# SAMC21_one.net
KiCad netlist of a schematic drawn in Altium Designer
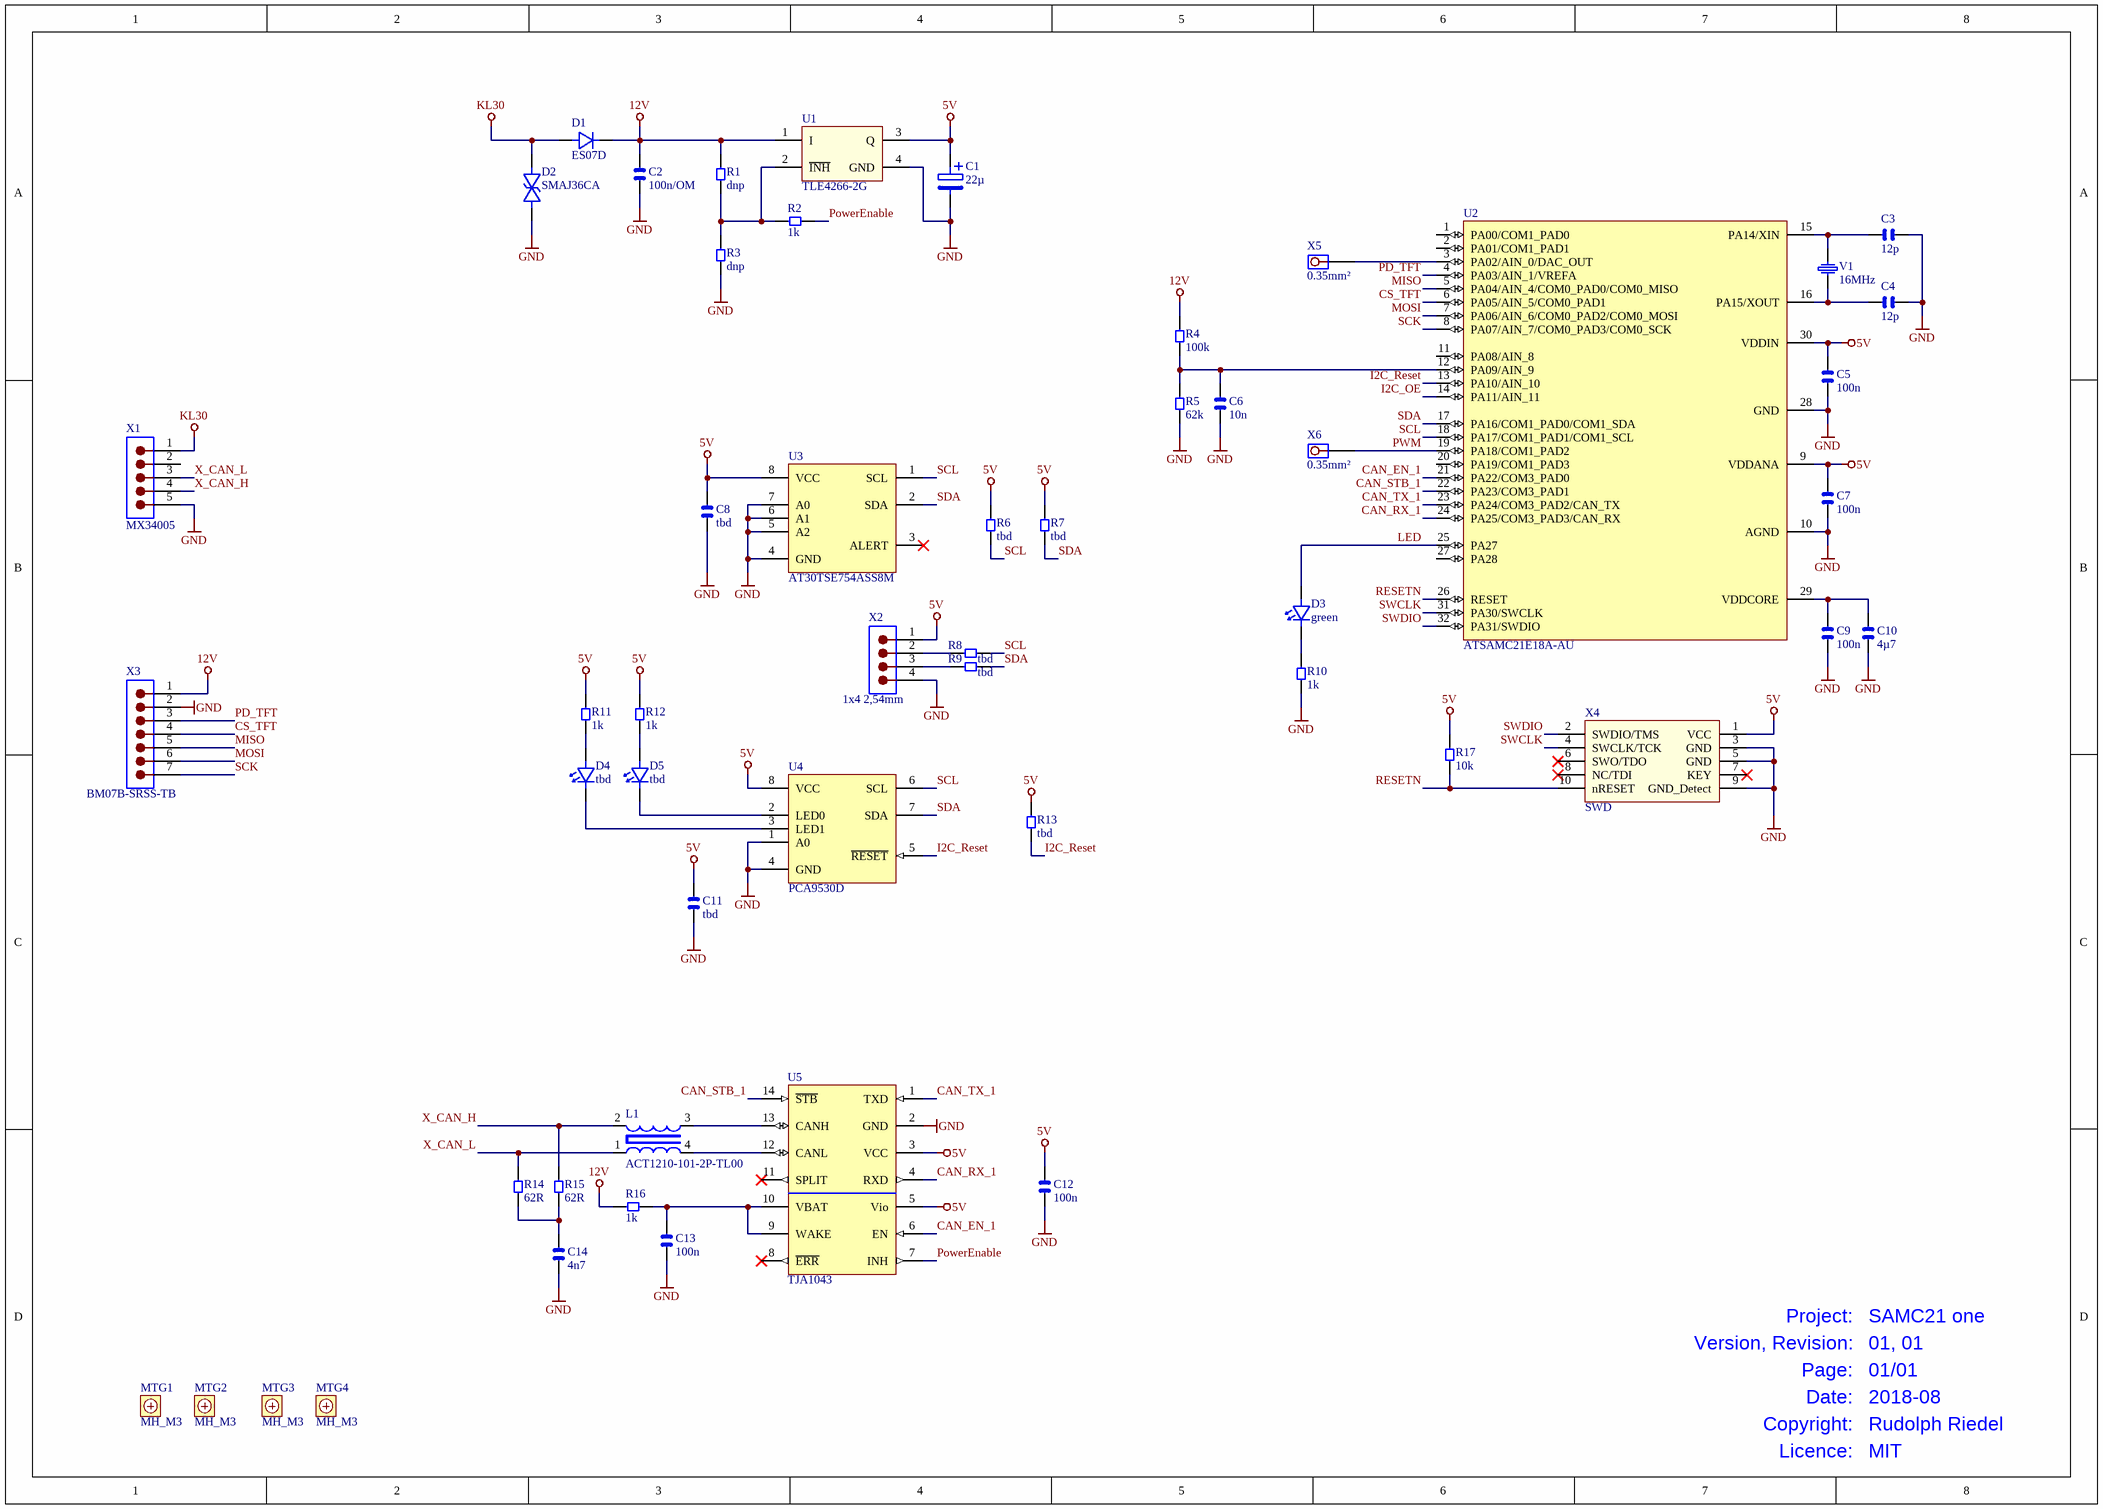
[diagram p0: SAMC21_one.SchDoc]

(export (version "E")
  (design (tool "Eeschema 10.0.6"))
  (components
    (comp (ref "C1")
      (value "22µ")
      (footprint "CAPMP3528X21N")
      (description "Tantalkondensator SMD Bauform B")
      (fields (field (name "PART NUMBER") "CAPMP_B") (field (name "ERSTELLER") "rriedel"))
      (libsource (lib "HW-Labor_GF") (part "CAPP_2_V2"))
    )
    (comp (ref "C2")
      (value "100n/OM")
      (footprint "CAPC2012X14L")
      (description "0805 Chip Capacitor")
      (fields (field (name "PART NUMBER") "CAPC_0805") (field (name "ERSTELLER") "rriedel"))
      (libsource (lib "HW-Labor_GF") (part "CAP_2_V2"))
    )
    (comp (ref "C3")
      (value "12p")
      (footprint "CAPC2012X14L")
      (description "0805 Chip Capacitor")
      (fields (field (name "PART NUMBER") "CAPC_0805") (field (name "ERSTELLER") "rriedel"))
      (libsource (lib "HW-Labor_GF") (part "CAP_2_V2"))
    )
    (comp (ref "C4")
      (value "12p")
      (footprint "CAPC2012X14L")
      (description "0805 Chip Capacitor")
      (fields (field (name "PART NUMBER") "CAPC_0805") (field (name "ERSTELLER") "rriedel"))
      (libsource (lib "HW-Labor_GF") (part "CAP_2_V2"))
    )
    (comp (ref "C5")
      (value "100n")
      (footprint "CAPC1608X09L")
      (description "0603 Chip Capacitor")
      (fields (field (name "PART NUMBER") "CAPC_0603") (field (name "ERSTELLER") "rriedel"))
      (libsource (lib "HW-Labor_GF") (part "CAP_2_V2"))
    )
    (comp (ref "C6")
      (value "10n")
      (footprint "CAPC2012X14L")
      (description "0805 Chip Capacitor")
      (fields (field (name "PART NUMBER") "CAPC_0805") (field (name "ERSTELLER") "rriedel"))
      (libsource (lib "HW-Labor_GF") (part "CAP_2_V2"))
    )
    (comp (ref "C7")
      (value "100n")
      (footprint "CAPC1608X09L")
      (description "0603 Chip Capacitor")
      (fields (field (name "PART NUMBER") "CAPC_0603") (field (name "ERSTELLER") "rriedel"))
      (libsource (lib "HW-Labor_GF") (part "CAP_2_V2"))
    )
    (comp (ref "C8")
      (value "tbd")
      (footprint "CAPC2012X14L")
      (description "0805 Chip Capacitor")
      (fields (field (name "PART NUMBER") "CAPC_0805") (field (name "ERSTELLER") "rriedel"))
      (libsource (lib "HW-Labor_GF") (part "CAP_2_V2"))
    )
    (comp (ref "C9")
      (value "100n")
      (footprint "CAPC1608X09L")
      (description "0603 Chip Capacitor")
      (fields (field (name "PART NUMBER") "CAPC_0603") (field (name "ERSTELLER") "rriedel"))
      (libsource (lib "HW-Labor_GF") (part "CAP_2_V2"))
    )
    (comp (ref "C10")
      (value "4µ7")
      (footprint "CAPC2012X14L")
      (description "0805 Chip Capacitor")
      (fields (field (name "PART NUMBER") "CAPC_0805") (field (name "ERSTELLER") "rriedel"))
      (libsource (lib "HW-Labor_GF") (part "CAP_2_V2"))
    )
    (comp (ref "C11")
      (value "tbd")
      (footprint "CAPC2012X14L")
      (description "0805 Chip Capacitor")
      (fields (field (name "PART NUMBER") "CAPC_0805") (field (name "ERSTELLER") "rriedel"))
      (libsource (lib "HW-Labor_GF") (part "CAP_2_V2"))
    )
    (comp (ref "C12")
      (value "100n")
      (footprint "CAPC2012X14L")
      (description "0805 Chip Capacitor")
      (fields (field (name "PART NUMBER") "CAPC_0805") (field (name "ERSTELLER") "rriedel"))
      (libsource (lib "HW-Labor_GF") (part "CAP_2_V2"))
    )
    (comp (ref "C13")
      (value "100n")
      (footprint "CAPC2012X14L")
      (description "0805 Chip Capacitor")
      (fields (field (name "PART NUMBER") "CAPC_0805") (field (name "ERSTELLER") "rriedel"))
      (libsource (lib "HW-Labor_GF") (part "CAP_2_V2"))
    )
    (comp (ref "C14")
      (value "4n7")
      (footprint "CAPC2012X14L")
      (description "0805 Chip Capacitor")
      (fields (field (name "PART NUMBER") "CAPC_0805") (field (name "ERSTELLER") "rriedel"))
      (libsource (lib "HW-Labor_GF") (part "CAP_2_V2"))
    )
    (comp (ref "D1")
      (value "ES07D")
      (footprint "DIOM2818X11N")
      (description "Ultrafast Rectifier Surface Mount,  IF 0.5A, VR 100V, DO-219AB, AEC-Q101")
      (fields (field (name "ERSTELLER") "rriedel"))
      (libsource (lib "HW-Labor_GF") (part "Diode_A2_K1"))
    )
    (comp (ref "D2")
      (value "SMAJ36CA")
      (footprint "DIOM5226X23N")
      (description "Transildiode Bidirectional 400W 36V")
      (fields (field (name "ERSTELLER") "rriedel"))
      (libsource (lib "HW-Labor_GF") (part "SMAJxxCA"))
    )
    (comp (ref "D3")
      (value "green")
      (footprint "DIOC2012X10N")
      (description "LED, 0805")
      (fields (field (name "PART NUMBER") "LED_0805") (field (name "ERSTELLER") "rriedel"))
      (libsource (lib "HW-Labor_GF") (part "LED_generic"))
    )
    (comp (ref "D4")
      (value "tbd")
      (footprint "DIOC2012X10N")
      (description "LED, 0805")
      (fields (field (name "PART NUMBER") "LED_0805") (field (name "ERSTELLER") "rriedel"))
      (libsource (lib "HW-Labor_GF") (part "LED_generic"))
    )
    (comp (ref "D5")
      (value "tbd")
      (footprint "DIOC2012X10N")
      (description "LED, 0805")
      (fields (field (name "PART NUMBER") "LED_0805") (field (name "ERSTELLER") "rriedel"))
      (libsource (lib "HW-Labor_GF") (part "LED_generic"))
    )
    (comp (ref "L1")
      (value "ACT1210-101-2P-TL00")
      (footprint "ACT1210")
      (description "Common Mode Filter,  -50°C ... +150°C, AEC-Q200")
      (fields
        (field (name "DISTRIBUTOR_1_PART_NUMBER") "2442838")
        (field (name "DISTRIBUTOR_2_PART_NUMBER") "445-172386-1-ND")
        (field (name "ERSTELLER") "rriedel")
      )
      (libsource (lib "HW-Labor_GF") (part "CAN_DROSSEL"))
    )
    (comp (ref "MTG1")
      (value "MH_M3")
      (footprint "HOLE_3_2MM")
      (description "Mounting-Hole for M3 screws")
      (fields (field (name "ERSTELLER") "rriedel"))
      (libsource (lib "HW-Labor_GF") (part "MTG_V1"))
    )
    (comp (ref "MTG2")
      (value "MH_M3")
      (footprint "HOLE_3_2MM")
      (description "Mounting-Hole for M3 screws")
      (fields (field (name "ERSTELLER") "rriedel"))
      (libsource (lib "HW-Labor_GF") (part "MTG_V1"))
    )
    (comp (ref "MTG3")
      (value "MH_M3")
      (footprint "HOLE_3_2MM")
      (description "Mounting-Hole for M3 screws")
      (fields (field (name "ERSTELLER") "rriedel"))
      (libsource (lib "HW-Labor_GF") (part "MTG_V1"))
    )
    (comp (ref "MTG4")
      (value "MH_M3")
      (footprint "HOLE_3_2MM")
      (description "Mounting-Hole for M3 screws")
      (fields (field (name "ERSTELLER") "rriedel"))
      (libsource (lib "HW-Labor_GF") (part "MTG_V1"))
    )
    (comp (ref "R1")
      (value "dnp")
      (footprint "RESC2012X06L")
      (description "0805 Chip Resistor")
      (fields (field (name "PART NUMBER") "RESC_0805") (field (name "ERSTELLER") "rriedel"))
      (libsource (lib "HW-Labor_GF") (part "RES_2_V2"))
    )
    (comp (ref "R2")
      (value "1k")
      (footprint "RESC2012X06L")
      (description "0805 Chip Resistor")
      (fields (field (name "PART NUMBER") "RESC_0805") (field (name "ERSTELLER") "rriedel"))
      (libsource (lib "HW-Labor_GF") (part "RES_2_V2"))
    )
    (comp (ref "R3")
      (value "dnp")
      (footprint "RESC2012X06L")
      (description "0805 Chip Resistor")
      (fields (field (name "PART NUMBER") "RESC_0805") (field (name "ERSTELLER") "rriedel"))
      (libsource (lib "HW-Labor_GF") (part "RES_2_V2"))
    )
    (comp (ref "R4")
      (value "100k")
      (footprint "RESC2012X06L")
      (description "0805 Chip Resistor")
      (fields (field (name "PART NUMBER") "RESC_0805") (field (name "ERSTELLER") "rriedel"))
      (libsource (lib "HW-Labor_GF") (part "RES_2_V2"))
    )
    (comp (ref "R5")
      (value "62k")
      (footprint "RESC2012X06L")
      (description "0805 Chip Resistor")
      (fields (field (name "PART NUMBER") "RESC_0805") (field (name "ERSTELLER") "rriedel"))
      (libsource (lib "HW-Labor_GF") (part "RES_2_V2"))
    )
    (comp (ref "R6")
      (value "tbd")
      (footprint "RESC2012X06L")
      (description "0805 Chip Resistor")
      (fields (field (name "PART NUMBER") "RESC_0805") (field (name "ERSTELLER") "rriedel"))
      (libsource (lib "HW-Labor_GF") (part "RES_2_V2"))
    )
    (comp (ref "R7")
      (value "tbd")
      (footprint "RESC2012X06L")
      (description "0805 Chip Resistor")
      (fields (field (name "PART NUMBER") "RESC_0805") (field (name "ERSTELLER") "rriedel"))
      (libsource (lib "HW-Labor_GF") (part "RES_2_V2"))
    )
    (comp (ref "R8")
      (value "tbd")
      (footprint "RESC2012X06L")
      (description "0805 Chip Resistor")
      (fields (field (name "PART NUMBER") "RESC_0805") (field (name "ERSTELLER") "rriedel"))
      (libsource (lib "HW-Labor_GF") (part "RES_2_V2"))
    )
    (comp (ref "R9")
      (value "tbd")
      (footprint "RESC2012X06L")
      (description "0805 Chip Resistor")
      (fields (field (name "PART NUMBER") "RESC_0805") (field (name "ERSTELLER") "rriedel"))
      (libsource (lib "HW-Labor_GF") (part "RES_2_V2"))
    )
    (comp (ref "R10")
      (value "1k")
      (footprint "RESC2012X06L")
      (description "0805 Chip Resistor")
      (fields (field (name "PART NUMBER") "RESC_0805") (field (name "ERSTELLER") "rriedel"))
      (libsource (lib "HW-Labor_GF") (part "RES_2_V2"))
    )
    (comp (ref "R11")
      (value "1k")
      (footprint "RESC2012X06L")
      (description "0805 Chip Resistor")
      (fields (field (name "PART NUMBER") "RESC_0805") (field (name "ERSTELLER") "rriedel"))
      (libsource (lib "HW-Labor_GF") (part "RES_2_V2"))
    )
    (comp (ref "R12")
      (value "1k")
      (footprint "RESC2012X06L")
      (description "0805 Chip Resistor")
      (fields (field (name "PART NUMBER") "RESC_0805") (field (name "ERSTELLER") "rriedel"))
      (libsource (lib "HW-Labor_GF") (part "RES_2_V2"))
    )
    (comp (ref "R13")
      (value "tbd")
      (footprint "RESC2012X06L")
      (description "0805 Chip Resistor")
      (fields (field (name "PART NUMBER") "RESC_0805") (field (name "ERSTELLER") "rriedel"))
      (libsource (lib "HW-Labor_GF") (part "RES_2_V2"))
    )
    (comp (ref "R14")
      (value "62R")
      (footprint "RESC3216X07N")
      (description "1206 Chip Resistor")
      (fields (field (name "PART NUMBER") "RESC_1206") (field (name "ERSTELLER") "rriedel"))
      (libsource (lib "HW-Labor_GF") (part "RES_2_V2"))
    )
    (comp (ref "R15")
      (value "62R")
      (footprint "RESC3216X07N")
      (description "1206 Chip Resistor")
      (fields (field (name "PART NUMBER") "RESC_1206") (field (name "ERSTELLER") "rriedel"))
      (libsource (lib "HW-Labor_GF") (part "RES_2_V2"))
    )
    (comp (ref "R16")
      (value "1k")
      (footprint "RESC2012X06L")
      (description "0805 Chip Resistor")
      (fields (field (name "PART NUMBER") "RESC_0805") (field (name "ERSTELLER") "rriedel"))
      (libsource (lib "HW-Labor_GF") (part "RES_2_V2"))
    )
    (comp (ref "R17")
      (value "10k")
      (footprint "RESC2012X06L")
      (description "0805 Chip Resistor")
      (fields (field (name "PART NUMBER") "RESC_0805") (field (name "ERSTELLER") "rriedel"))
      (libsource (lib "HW-Labor_GF") (part "RES_2_V2"))
    )
    (comp (ref "U1")
      (value "TLE4266-2G")
      (footprint "SOT230P700X180-4N")
      (description "150 mA LDO, Vout = 5,0V, 2%, Enable")
      (fields (field (name "ERSTELLER") "rriedel"))
      (libsource (lib "HW-Labor_GF") (part "LDO_SOT223_EN"))
    )
    (comp (ref "U2")
      (value "ATSAMC21E18A-AU")
      (footprint "TQFP80P900X900X120-32N")
      (description "32-bit Microcontroller, 48MHz Cortex M0, 256k FLASH,  1x CAN-FD, -40…85°C")
      (fields (field (name "ERSTELLER") "rriedel"))
      (libsource (lib "HW-Labor_GF") (part "ATSAMC21E1xA"))
    )
    (comp (ref "U3")
      (value "AT30TSE754ASS8M")
      (footprint "SOIC127P600X175-8N")
      (description "I2C Digital Temperature Sensor and EEPROM")
      (fields (field (name "ERSTELLER") "rriedel"))
      (libsource (lib "HW-Labor_GF") (part "AT30TSE75xAxx8M"))
    )
    (comp (ref "U4")
      (value "PCA9530D")
      (footprint "TSOP65P640X120-8N")
      (description "2-bit I2C LED dimmer")
      (fields (field (name "ERSTELLER") "rriedel"))
      (libsource (lib "HW-Labor_GF") (part "PCA9530"))
    )
    (comp (ref "U5")
      (value "TJA1043")
      (footprint "SOIC127P600X175-14N")
      (description "HS Can Transceiver with wake-up Tvj= -40 to 150 °C")
      (fields (field (name "PART NUMBER") "TJA1043T") (field (name "ERSTELLER") "rriedel"))
      (libsource (lib "HW-Labor_GF") (part "TJA1043"))
    )
    (comp (ref "V1")
      (value "16MHz")
      (footprint "NX3225Gx")
      (description "16.000MHz Crystal SMD, 3.2x2.5mm, 8pF, 50ppm,  -40..+150°C")
      (fields
        (field (name "PART NUMBER") "NX3225GB-16.000000MHZ")
        (field (name "DISTRIBUTOR_1_PART_NUMBER") "644-1233-1-ND")
        (field (name "ERSTELLER") "rriedel")
      )
      (libsource (lib "HW-Labor_GF") (part "XTAL_2_V1"))
    )
    (comp (ref "X1")
      (value "MX34005")
      (footprint "MX34005")
      (description "PCB Header, Automotive, single row, 5 pins")
      (fields (field (name "ERSTELLER") "rriedel"))
      (libsource (lib "HW-Labor_GF") (part "CONM_1x5_V2"))
    )
    (comp (ref "X2")
      (value "1x4 2,54mm")
      (footprint "PINH_1x04_2_54mm")
      (description "Pin-Header 2,54 mm 4pins")
      (fields (field (name "PART NUMBER") "PINH_1x4_2_54") (field (name "ERSTELLER") "rriedel"))
      (libsource (lib "HW-Labor_GF") (part "CONM_1x4_V2"))
    )
    (comp (ref "X3")
      (value "BM07B-SRSS-TB")
      (footprint "BM07B-SRSS-TB")
      (description "JST PCB Header SH, 7pins, 1,0mm, -25°C to +85°C")
      (fields
        (field (name "PART NUMBER") "SM07B-SRSS-TB")
        (field (name "DISTRIBUTOR_1_PART_NUMBER") "546-8798")
        (field (name "ERSTELLER") "rriedel")
      )
      (libsource (lib "HW-Labor_GF") (part "CONM_1x7_V2"))
    )
    (comp (ref "X4")
      (value "SWD")
      (footprint "FTSH-105-01-L-DV-K")
      (description "ARM Debug-Header 2x5 1,27 mm")
      (fields (field (name "ERSTELLER") "rriedel"))
      (libsource (lib "HW-Labor_GF") (part "SWD"))
    )
    (comp (ref "X5")
      (value "0.35mm²")
      (footprint "PAD035X160")
      (description "Wire pad 0,35mm²")
      (fields (field (name "PART NUMBER") "PAD035") (field (name "ERSTELLER") "rriedel"))
      (libsource (lib "HW-Labor_GF") (part "PADxxx_1"))
    )
    (comp (ref "X6")
      (value "0.35mm²")
      (footprint "PAD035X160")
      (description "Wire pad 0,35mm²")
      (fields (field (name "PART NUMBER") "PAD035") (field (name "ERSTELLER") "rriedel"))
      (libsource (lib "HW-Labor_GF") (part "PADxxx_1"))
    )
  )
  (nets
    (net (code "1") (name "/CAN_EN_1") (class "Default")
      (node (ref "U2") (pin "21") (pinfunction "PA22/COM3_PAD0_21") (pintype "bidirectional"))
      (node (ref "U5") (pin "6") (pinfunction "EN_6") (pintype "input"))
    )
    (net (code "2") (name "/CAN_RX_1") (class "Default")
      (node (ref "U2") (pin "24") (pinfunction "PA25/COM3_PAD3/CAN_RX_24") (pintype "bidirectional"))
      (node (ref "U5") (pin "4") (pinfunction "RXD_4") (pintype "output"))
    )
    (net (code "3") (name "/CAN_STB_1") (class "Default")
      (node (ref "U2") (pin "22") (pinfunction "PA23/COM3_PAD1_22") (pintype "bidirectional"))
      (node (ref "U5") (pin "14") (pinfunction "~{STB}_14") (pintype "input"))
    )
    (net (code "4") (name "/CAN_TX_1") (class "Default")
      (node (ref "U2") (pin "23") (pinfunction "PA24/COM3_PAD2/CAN_TX_23") (pintype "bidirectional"))
      (node (ref "U5") (pin "1") (pinfunction "TXD_1") (pintype "input"))
    )
    (net (code "5") (name "/CS_TFT") (class "Default")
      (node (ref "U2") (pin "6") (pinfunction "PA05/AIN_5/COM0_PAD1_6") (pintype "bidirectional"))
      (node (ref "X3") (pin "4") (pinfunction "4_4") (pintype "passive"))
    )
    (net (code "6") (name "/I2C_OE") (class "Default")
      (node (ref "U2") (pin "14") (pinfunction "PA11/AIN_11_14") (pintype "bidirectional"))
    )
    (net (code "7") (name "/I2C_Reset") (class "Default")
      (node (ref "R13") (pin "1") (pinfunction "1_1") (pintype "passive"))
      (node (ref "U2") (pin "13") (pinfunction "PA10/AIN_10_13") (pintype "bidirectional"))
      (node (ref "U4") (pin "5") (pinfunction "RESET_5") (pintype "input"))
    )
    (net (code "8") (name "/LED") (class "Default")
      (node (ref "D3") (pin "2") (pinfunction "2_2") (pintype "passive"))
      (node (ref "U2") (pin "25") (pinfunction "PA27_25") (pintype "bidirectional"))
    )
    (net (code "9") (name "/MISO") (class "Default")
      (node (ref "U2") (pin "5") (pinfunction "PA04/AIN_4/COM0_PAD0/COM0_MISO_5") (pintype "bidirectional"))
      (node (ref "X3") (pin "5") (pinfunction "5_5") (pintype "passive"))
    )
    (net (code "10") (name "/MOSI") (class "Default")
      (node (ref "U2") (pin "7") (pinfunction "PA06/AIN_6/COM0_PAD2/COM0_MOSI_7") (pintype "bidirectional"))
      (node (ref "X3") (pin "6") (pinfunction "6_6") (pintype "passive"))
    )
    (net (code "11") (name "/PD_TFT") (class "Default")
      (node (ref "U2") (pin "4") (pinfunction "PA03/AIN_1/VREFA_4") (pintype "bidirectional"))
      (node (ref "X3") (pin "3") (pinfunction "3_3") (pintype "passive"))
    )
    (net (code "12") (name "/PWM") (class "Default")
      (node (ref "U2") (pin "19") (pinfunction "PA18/COM1_PAD2_19") (pintype "bidirectional"))
      (node (ref "X6") (pin "1") (pinfunction "1_1") (pintype "passive"))
    )
    (net (code "13") (name "/PowerEnable") (class "Default")
      (node (ref "R2") (pin "1") (pinfunction "1_1") (pintype "passive"))
      (node (ref "U5") (pin "7") (pinfunction "INH_7") (pintype "output"))
    )
    (net (code "14") (name "/RESETN") (class "Default")
      (node (ref "R17") (pin "1") (pinfunction "1_1") (pintype "passive"))
      (node (ref "U2") (pin "26") (pinfunction "RESET_26") (pintype "bidirectional"))
      (node (ref "X4") (pin "10") (pinfunction "nRESET_10") (pintype "passive"))
    )
    (net (code "15") (name "/SCK") (class "Default")
      (node (ref "U2") (pin "8") (pinfunction "PA07/AIN_7/COM0_PAD3/COM0_SCK_8") (pintype "bidirectional"))
      (node (ref "X3") (pin "7") (pinfunction "7_7") (pintype "passive"))
    )
    (net (code "16") (name "/SCL") (class "Default")
      (node (ref "R6") (pin "1") (pinfunction "1_1") (pintype "passive"))
      (node (ref "R8") (pin "2") (pinfunction "2_2") (pintype "passive"))
      (node (ref "U2") (pin "18") (pinfunction "PA17/COM1_PAD1/COM1_SCL_18") (pintype "bidirectional"))
      (node (ref "U3") (pin "1") (pinfunction "SCL_1") (pintype "passive"))
      (node (ref "U4") (pin "6") (pinfunction "SCL_6") (pintype "passive"))
    )
    (net (code "17") (name "/SDA") (class "Default")
      (node (ref "R7") (pin "1") (pinfunction "1_1") (pintype "passive"))
      (node (ref "R9") (pin "2") (pinfunction "2_2") (pintype "passive"))
      (node (ref "U2") (pin "17") (pinfunction "PA16/COM1_PAD0/COM1_SDA_17") (pintype "bidirectional"))
      (node (ref "U3") (pin "2") (pinfunction "SDA_2") (pintype "passive"))
      (node (ref "U4") (pin "7") (pinfunction "SDA_7") (pintype "passive"))
    )
    (net (code "18") (name "/SWCLK") (class "Default")
      (node (ref "U2") (pin "31") (pinfunction "PA30/SWCLK_31") (pintype "bidirectional"))
      (node (ref "X4") (pin "4") (pinfunction "SWCLK/TCK_4") (pintype "passive"))
    )
    (net (code "19") (name "/SWDIO") (class "Default")
      (node (ref "U2") (pin "32") (pinfunction "PA31/SWDIO_32") (pintype "bidirectional"))
      (node (ref "X4") (pin "2") (pinfunction "SWDIO/TMS_2") (pintype "passive"))
    )
    (net (code "20") (name "/X_CAN_H") (class "Default")
      (node (ref "L1") (pin "2") (pintype "passive"))
      (node (ref "R15") (pin "2") (pinfunction "2_2") (pintype "passive"))
      (node (ref "X1") (pin "4") (pinfunction "4_4") (pintype "passive"))
    )
    (net (code "21") (name "/X_CAN_L") (class "Default")
      (node (ref "L1") (pin "1") (pintype "passive"))
      (node (ref "R14") (pin "2") (pinfunction "2_2") (pintype "passive"))
      (node (ref "X1") (pin "3") (pinfunction "3_3") (pintype "passive"))
    )
    (net (code "22") (name "5V") (class "Default")
      (node (ref "C1") (pin "1") (pinfunction "1_1") (pintype "passive"))
      (node (ref "C11") (pin "2") (pinfunction "2_2") (pintype "passive"))
      (node (ref "C12") (pin "2") (pinfunction "2_2") (pintype "passive"))
      (node (ref "C5") (pin "2") (pinfunction "2_2") (pintype "passive"))
      (node (ref "C7") (pin "2") (pinfunction "2_2") (pintype "passive"))
      (node (ref "C8") (pin "2") (pinfunction "2_2") (pintype "passive"))
      (node (ref "R11") (pin "2") (pinfunction "2_2") (pintype "passive"))
      (node (ref "R12") (pin "2") (pinfunction "2_2") (pintype "passive"))
      (node (ref "R13") (pin "2") (pinfunction "2_2") (pintype "passive"))
      (node (ref "R17") (pin "2") (pinfunction "2_2") (pintype "passive"))
      (node (ref "R6") (pin "2") (pinfunction "2_2") (pintype "passive"))
      (node (ref "R7") (pin "2") (pinfunction "2_2") (pintype "passive"))
      (node (ref "U1") (pin "3") (pinfunction "Q_3") (pintype "passive"))
      (node (ref "U2") (pin "30") (pinfunction "VDDIN_30") (pintype "power_in"))
      (node (ref "U2") (pin "9") (pinfunction "VDDANA_9") (pintype "power_in"))
      (node (ref "U3") (pin "8") (pinfunction "VCC_8") (pintype "power_in"))
      (node (ref "U4") (pin "8") (pinfunction "VCC_8") (pintype "power_in"))
      (node (ref "U5") (pin "3") (pinfunction "VCC_3") (pintype "power_in"))
      (node (ref "U5") (pin "5") (pinfunction "Vio_5") (pintype "power_in"))
      (node (ref "X2") (pin "1") (pinfunction "1_1") (pintype "passive"))
      (node (ref "X4") (pin "1") (pinfunction "VCC_1") (pintype "power_in"))
    )
    (net (code "23") (name "12V") (class "Default")
      (node (ref "C2") (pin "2") (pinfunction "2_2") (pintype "passive"))
      (node (ref "D1") (pin "1") (pinfunction "1_1") (pintype "passive"))
      (node (ref "R1") (pin "2") (pinfunction "2_2") (pintype "passive"))
      (node (ref "R16") (pin "1") (pinfunction "1_1") (pintype "passive"))
      (node (ref "R4") (pin "2") (pinfunction "2_2") (pintype "passive"))
      (node (ref "U1") (pin "1") (pinfunction "I_1") (pintype "passive"))
      (node (ref "X3") (pin "1") (pinfunction "1_1") (pintype "passive"))
    )
    (net (code "24") (name "GND") (class "Default")
      (node (ref "C1") (pin "2") (pinfunction "2_2") (pintype "passive"))
      (node (ref "C10") (pin "1") (pinfunction "1_1") (pintype "passive"))
      (node (ref "C11") (pin "1") (pinfunction "1_1") (pintype "passive"))
      (node (ref "C12") (pin "1") (pinfunction "1_1") (pintype "passive"))
      (node (ref "C13") (pin "1") (pinfunction "1_1") (pintype "passive"))
      (node (ref "C14") (pin "1") (pinfunction "1_1") (pintype "passive"))
      (node (ref "C2") (pin "1") (pinfunction "1_1") (pintype "passive"))
      (node (ref "C3") (pin "2") (pinfunction "2_2") (pintype "passive"))
      (node (ref "C4") (pin "2") (pinfunction "2_2") (pintype "passive"))
      (node (ref "C5") (pin "1") (pinfunction "1_1") (pintype "passive"))
      (node (ref "C6") (pin "1") (pinfunction "1_1") (pintype "passive"))
      (node (ref "C7") (pin "1") (pinfunction "1_1") (pintype "passive"))
      (node (ref "C8") (pin "1") (pinfunction "1_1") (pintype "passive"))
      (node (ref "C9") (pin "1") (pinfunction "1_1") (pintype "passive"))
      (node (ref "D2") (pin "1") (pinfunction "1_1") (pintype "passive"))
      (node (ref "R10") (pin "1") (pinfunction "1_1") (pintype "passive"))
      (node (ref "R3") (pin "1") (pinfunction "1_1") (pintype "passive"))
      (node (ref "R5") (pin "1") (pinfunction "1_1") (pintype "passive"))
      (node (ref "U1") (pin "4") (pinfunction "GND_4") (pintype "passive"))
      (node (ref "U2") (pin "10") (pinfunction "AGND_10") (pintype "power_in"))
      (node (ref "U2") (pin "28") (pinfunction "GND_28") (pintype "power_in"))
      (node (ref "U3") (pin "4") (pinfunction "GND_4") (pintype "power_in"))
      (node (ref "U3") (pin "5") (pinfunction "A2_5") (pintype "passive"))
      (node (ref "U3") (pin "6") (pinfunction "A1_6") (pintype "passive"))
      (node (ref "U3") (pin "7") (pinfunction "A0_7") (pintype "passive"))
      (node (ref "U4") (pin "1") (pinfunction "A0_1") (pintype "passive"))
      (node (ref "U4") (pin "4") (pinfunction "GND_4") (pintype "power_in"))
      (node (ref "U5") (pin "2") (pinfunction "GND_2") (pintype "power_in"))
      (node (ref "X1") (pin "5") (pinfunction "5_5") (pintype "passive"))
      (node (ref "X2") (pin "4") (pinfunction "4_4") (pintype "passive"))
      (node (ref "X3") (pin "2") (pinfunction "2_2") (pintype "passive"))
      (node (ref "X4") (pin "3") (pinfunction "GND_3") (pintype "power_in"))
      (node (ref "X4") (pin "5") (pinfunction "GND_5") (pintype "power_in"))
      (node (ref "X4") (pin "9") (pinfunction "GND_Detect_9") (pintype "power_in"))
    )
    (net (code "25") (name "KL30") (class "Default")
      (node (ref "D1") (pin "2") (pinfunction "2_2") (pintype "passive"))
      (node (ref "D2") (pin "2") (pinfunction "2_2") (pintype "passive"))
      (node (ref "X1") (pin "1") (pinfunction "1_1") (pintype "passive"))
    )
    (net (code "26") (name "Net-(C14-Pad2)") (class "Default")
      (node (ref "C14") (pin "2") (pinfunction "2_2") (pintype "passive"))
      (node (ref "R14") (pin "1") (pinfunction "1_1") (pintype "passive"))
      (node (ref "R15") (pin "1") (pinfunction "1_1") (pintype "passive"))
    )
    (net (code "27") (name "Net-(D3-Pad1)") (class "Default")
      (node (ref "D3") (pin "1") (pinfunction "1_1") (pintype "passive"))
      (node (ref "R10") (pin "2") (pinfunction "2_2") (pintype "passive"))
    )
    (net (code "28") (name "Net-(D4-Pad2)") (class "Default")
      (node (ref "D4") (pin "2") (pinfunction "2_2") (pintype "passive"))
      (node (ref "R11") (pin "1") (pinfunction "1_1") (pintype "passive"))
    )
    (net (code "29") (name "Net-(D5-Pad2)") (class "Default")
      (node (ref "D5") (pin "2") (pinfunction "2_2") (pintype "passive"))
      (node (ref "R12") (pin "1") (pinfunction "1_1") (pintype "passive"))
    )
    (net (code "30") (name "Net-(R8-Pad1)") (class "Default")
      (node (ref "R8") (pin "1") (pinfunction "1_1") (pintype "passive"))
      (node (ref "X2") (pin "2") (pinfunction "2_2") (pintype "passive"))
    )
    (net (code "31") (name "Net-(R9-Pad1)") (class "Default")
      (node (ref "R9") (pin "1") (pinfunction "1_1") (pintype "passive"))
      (node (ref "X2") (pin "3") (pinfunction "3_3") (pintype "passive"))
    )
    (net (code "32") (name "Net-(U1-~{INH})") (class "Default")
      (node (ref "R1") (pin "1") (pinfunction "1_1") (pintype "passive"))
      (node (ref "R2") (pin "2") (pinfunction "2_2") (pintype "passive"))
      (node (ref "R3") (pin "2") (pinfunction "2_2") (pintype "passive"))
      (node (ref "U1") (pin "2") (pinfunction "~{INH}_2") (pintype "passive"))
    )
    (net (code "33") (name "Net-(U2-PA02{slash}AIN_0{slash}DAC_OUT)") (class "Default")
      (node (ref "U2") (pin "3") (pinfunction "PA02/AIN_0/DAC_OUT_3") (pintype "bidirectional"))
      (node (ref "X5") (pin "1") (pinfunction "1_1") (pintype "passive"))
    )
    (net (code "34") (name "Net-(U2-PA09{slash}AIN_9)") (class "Default")
      (node (ref "C6") (pin "2") (pinfunction "2_2") (pintype "passive"))
      (node (ref "R4") (pin "1") (pinfunction "1_1") (pintype "passive"))
      (node (ref "R5") (pin "2") (pinfunction "2_2") (pintype "passive"))
      (node (ref "U2") (pin "12") (pinfunction "PA09/AIN_9_12") (pintype "bidirectional"))
    )
    (net (code "35") (name "Net-(U2-PA14{slash}XIN)") (class "Default")
      (node (ref "C3") (pin "1") (pinfunction "1_1") (pintype "passive"))
      (node (ref "U2") (pin "15") (pinfunction "PA14/XIN_15") (pintype "passive"))
      (node (ref "V1") (pin "2") (pinfunction "2_2") (pintype "passive"))
    )
    (net (code "36") (name "Net-(U2-PA15{slash}XOUT)") (class "Default")
      (node (ref "C4") (pin "1") (pinfunction "1_1") (pintype "passive"))
      (node (ref "U2") (pin "16") (pinfunction "PA15/XOUT_16") (pintype "passive"))
      (node (ref "V1") (pin "1") (pinfunction "1_1") (pintype "passive"))
    )
    (net (code "37") (name "Net-(U2-VDDCORE)") (class "Default")
      (node (ref "C10") (pin "2") (pinfunction "2_2") (pintype "passive"))
      (node (ref "C9") (pin "2") (pinfunction "2_2") (pintype "passive"))
      (node (ref "U2") (pin "29") (pinfunction "VDDCORE_29") (pintype "passive"))
    )
    (net (code "38") (name "Net-(U4-LED0)") (class "Default")
      (node (ref "D5") (pin "1") (pinfunction "1_1") (pintype "passive"))
      (node (ref "U4") (pin "2") (pinfunction "LED0_2") (pintype "passive"))
    )
    (net (code "39") (name "Net-(U4-LED1)") (class "Default")
      (node (ref "D4") (pin "1") (pinfunction "1_1") (pintype "passive"))
      (node (ref "U4") (pin "3") (pinfunction "LED1_3") (pintype "passive"))
    )
    (net (code "40") (name "Net-(U5-CANH)") (class "Default")
      (node (ref "L1") (pin "3") (pintype "passive"))
      (node (ref "U5") (pin "13") (pinfunction "CANH_13") (pintype "bidirectional"))
    )
    (net (code "41") (name "Net-(U5-CANL)") (class "Default")
      (node (ref "L1") (pin "4") (pintype "passive"))
      (node (ref "U5") (pin "12") (pinfunction "CANL_12") (pintype "bidirectional"))
    )
    (net (code "42") (name "Net-(U5-VBAT)") (class "Default")
      (node (ref "C13") (pin "2") (pinfunction "2_2") (pintype "passive"))
      (node (ref "R16") (pin "2") (pinfunction "2_2") (pintype "passive"))
      (node (ref "U5") (pin "10") (pinfunction "VBAT_10") (pintype "power_in"))
      (node (ref "U5") (pin "9") (pinfunction "WAKE_9") (pintype "passive"))
    )
    (net (code "43") (name "unconnected-(U2-PA00{slash}COM1_PAD0-Pad1)") (class "Default")
      (node (ref "U2") (pin "1") (pinfunction "PA00/COM1_PAD0_1") (pintype "bidirectional"))
    )
    (net (code "44") (name "unconnected-(U2-PA01{slash}COM1_PAD1-Pad2)") (class "Default")
      (node (ref "U2") (pin "2") (pinfunction "PA01/COM1_PAD1_2") (pintype "bidirectional"))
    )
    (net (code "45") (name "unconnected-(U2-PA08{slash}AIN_8-Pad11)") (class "Default")
      (node (ref "U2") (pin "11") (pinfunction "PA08/AIN_8_11") (pintype "bidirectional"))
    )
    (net (code "46") (name "unconnected-(U2-PA19{slash}COM1_PAD3-Pad20)") (class "Default")
      (node (ref "U2") (pin "20") (pinfunction "PA19/COM1_PAD3_20") (pintype "bidirectional"))
    )
    (net (code "47") (name "unconnected-(U2-PA28-Pad27)") (class "Default")
      (node (ref "U2") (pin "27") (pinfunction "PA28_27") (pintype "bidirectional"))
    )
    (net (code "48") (name "unconnected-(U3-ALERT-Pad3)") (class "Default")
      (node (ref "U3") (pin "3") (pinfunction "ALERT_3") (pintype "open_collector+no_connect"))
    )
    (net (code "49") (name "unconnected-(U5-SPLIT-Pad11)") (class "Default")
      (node (ref "U5") (pin "11") (pinfunction "SPLIT_11") (pintype "output+no_connect"))
    )
    (net (code "50") (name "unconnected-(U5-~{ERR}-Pad8)") (class "Default")
      (node (ref "U5") (pin "8") (pinfunction "~{ERR}_8") (pintype "output+no_connect"))
    )
    (net (code "51") (name "unconnected-(X1-Pad2)") (class "Default")
      (node (ref "X1") (pin "2") (pinfunction "2_2") (pintype "passive"))
    )
    (net (code "52") (name "unconnected-(X4-KEY-Pad7)") (class "Default")
      (node (ref "X4") (pin "7") (pinfunction "KEY_7") (pintype "passive+no_connect"))
    )
    (net (code "53") (name "unconnected-(X4-NC{slash}TDI-Pad8)") (class "Default")
      (node (ref "X4") (pin "8") (pinfunction "NC/TDI_8") (pintype "passive+no_connect"))
    )
    (net (code "54") (name "unconnected-(X4-SWO{slash}TDO-Pad6)") (class "Default")
      (node (ref "X4") (pin "6") (pinfunction "SWO/TDO_6") (pintype "passive+no_connect"))
    )
  )
)
